# Relay1_Block.net
KiCad netlist of a schematic drawn in Altium Designer
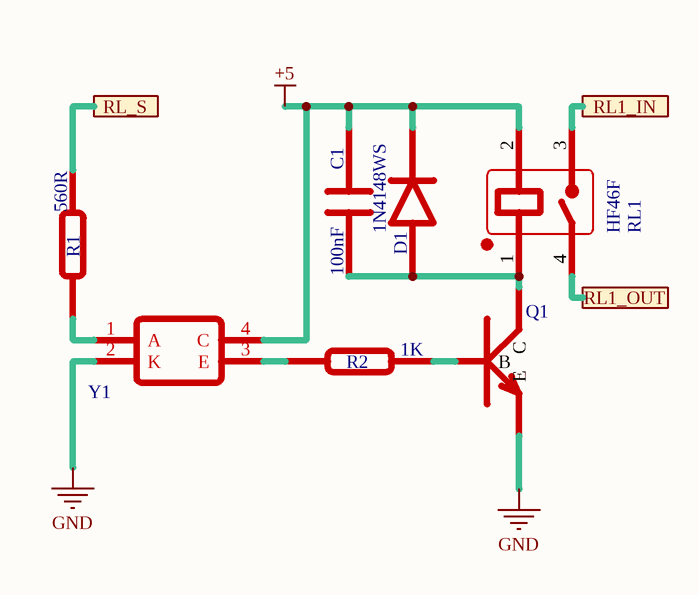
[diagram p0: Relay1_Block.SchDoc]

(export (version "E")
  (design (tool "Eeschema 10.0.6"))
  (components
    (comp (ref "C1")
      (value "100nF")
      (footprint "C0805")
      (description "Ceramic Capacitor")
      (libsource (lib "CTAI-Library") (part "CAP-CER"))
    )
    (comp (ref "D1")
      (value "1N4148WS")
      (footprint "SMA")
      (description "Small Signal Diode")
      (libsource (lib "CTAI-Library") (part "1N4148WS"))
    )
    (comp (ref "Q1")
      (value "S8050")
      (footprint "SOT-23")
      (description "NPN Transistors 0.5A Collector to Emitter 25V")
      (libsource (lib "CTAI-Library") (part "S8050"))
    )
    (comp (ref "R1")
      (value "560R")
      (footprint "R0603")
      (description "Resistor")
      (libsource (lib "CTAI-Library") (part "Resistor"))
    )
    (comp (ref "R2")
      (value "1K")
      (footprint "R0603")
      (description "Resistor")
      (libsource (lib "CTAI-Library") (part "Resistor"))
    )
    (comp (ref "RL1")
      (value "HF46F")
      (footprint "HF-46-X")
      (description "Relay 4 Pin")
      (libsource (lib "CTAI-Library") (part "HF46F"))
    )
    (comp (ref "Y1")
      (value "PHOTOCOUPLER")
      (footprint "SOP-4")
      (description "Photo-Coupler")
      (libsource (lib "CTAI-Library") (part "PC817"))
    )
  )
  (nets
    (net (code "1") (name "+5") (class "Default")
      (node (ref "C1") (pin "2") (pintype "passive"))
      (node (ref "D1") (pin "K") (pinfunction "K_K") (pintype "passive"))
      (node (ref "RL1") (pin "2") (pinfunction "2_2") (pintype "passive"))
      (node (ref "Y1") (pin "4") (pinfunction "C_4") (pintype "passive"))
    )
    (net (code "2") (name "/RL1_IN") (class "Default")
      (node (ref "RL1") (pin "3") (pinfunction "3_3") (pintype "passive"))
    )
    (net (code "3") (name "/RL1_OUT") (class "Default")
      (node (ref "RL1") (pin "4") (pinfunction "4_4") (pintype "passive"))
    )
    (net (code "4") (name "/RL_S") (class "Default")
      (node (ref "R1") (pin "1") (pinfunction "1_1") (pintype "passive"))
    )
    (net (code "5") (name "GND") (class "Default")
      (node (ref "Q1") (pin "2") (pinfunction "E_2") (pintype "passive"))
      (node (ref "Y1") (pin "2") (pinfunction "K_2") (pintype "passive"))
    )
    (net (code "6") (name "Net-(Q1-B)") (class "Default")
      (node (ref "Q1") (pin "1") (pinfunction "B_1") (pintype "passive"))
      (node (ref "R2") (pin "1") (pinfunction "1_1") (pintype "passive"))
    )
    (net (code "7") (name "Net-(Q1-C)") (class "Default")
      (node (ref "C1") (pin "1") (pintype "passive"))
      (node (ref "D1") (pin "A") (pinfunction "A_A") (pintype "passive"))
      (node (ref "Q1") (pin "3") (pinfunction "C_3") (pintype "passive"))
      (node (ref "RL1") (pin "1") (pinfunction "1_1") (pintype "passive"))
    )
    (net (code "8") (name "Net-(Y1-A)") (class "Default")
      (node (ref "R1") (pin "2") (pinfunction "2_2") (pintype "passive"))
      (node (ref "Y1") (pin "1") (pinfunction "A_1") (pintype "passive"))
    )
    (net (code "9") (name "Net-(Y1-E)") (class "Default")
      (node (ref "R2") (pin "2") (pinfunction "2_2") (pintype "passive"))
      (node (ref "Y1") (pin "3") (pinfunction "E_3") (pintype "passive"))
    )
  )
)
